# design.net
KiCad netlist of a schematic drawn in Altium Designer
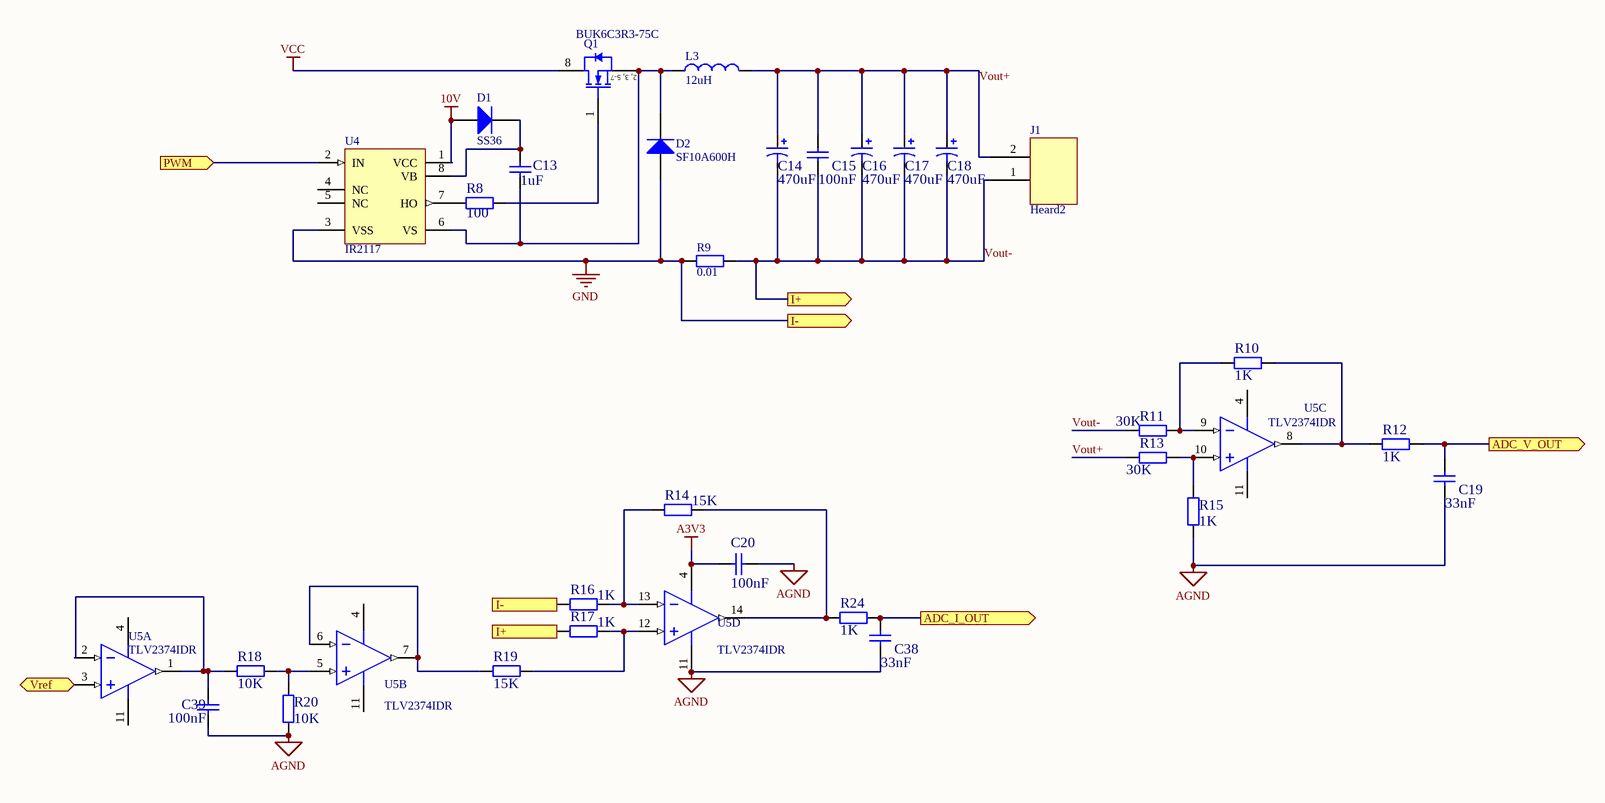
[diagram p0: 主电路.SchDoc]

(export (version "E")
  (design (tool "Eeschema 10.0.6"))
  (components
    (comp (ref "C13")
      (value "1uF")
      (footprint "0805R")
      (description "Capacitor")
      (fields (field (name "PUBLISHER") "Altium Limited"))
      (libsource (lib "Miscellaneous Devices") (part "Cap"))
    )
    (comp (ref "C14")
      (value "470uF")
      (footprint "RB-220T")
      (description "Polarized Capacitor (Radial)")
      (fields (field (name "Comment") "Cap Pol1") (field (name "PUBLISHER") "Altium Limited"))
      (libsource (lib "Miscellaneous Devices") (part "Cap Pol1"))
    )
    (comp (ref "C15")
      (value "100nF")
      (footprint "0805_C")
      (description "贴片电容")
      (libsource (lib "Miscellaneous Devices LC") (part "0805 100nF(104) 10% 50V"))
    )
    (comp (ref "C16")
      (value "470uF")
      (footprint "RB-220T")
      (description "Polarized Capacitor (Radial)")
      (fields (field (name "Comment") "Cap Pol1") (field (name "PUBLISHER") "Altium Limited"))
      (libsource (lib "Miscellaneous Devices") (part "Cap Pol1"))
    )
    (comp (ref "C17")
      (value "470uF")
      (footprint "RB-220T")
      (description "Polarized Capacitor (Radial)")
      (fields (field (name "Comment") "Cap Pol1") (field (name "PUBLISHER") "Altium Limited"))
      (libsource (lib "Miscellaneous Devices") (part "Cap Pol1"))
    )
    (comp (ref "C18")
      (value "470uF")
      (footprint "RB-220T")
      (description "Polarized Capacitor (Radial)")
      (fields (field (name "Comment") "Cap Pol1") (field (name "PUBLISHER") "Altium Limited"))
      (libsource (lib "Miscellaneous Devices") (part "Cap Pol1"))
    )
    (comp (ref "C19")
      (value "33nF")
      (footprint "0805_C")
      (description "贴片电容")
      (libsource (lib "Miscellaneous Devices LC") (part "0805 100nF(104) 10% 50V"))
    )
    (comp (ref "C20")
      (value "100nF")
      (footprint "0805_C")
      (description "贴片电容")
      (libsource (lib "Miscellaneous Devices LC") (part "0805 100nF(104) 10% 50V"))
    )
    (comp (ref "C38")
      (value "33nF")
      (footprint "0805_C")
      (description "贴片电容")
      (libsource (lib "Miscellaneous Devices LC") (part "0805 100nF(104) 10% 50V"))
    )
    (comp (ref "C39")
      (value "100nF")
      (footprint "0805_C")
      (description "贴片电容")
      (libsource (lib "Miscellaneous Devices LC") (part "0805 100nF(104) 10% 50V"))
    )
    (comp (ref "D1")
      (value "SS36")
      (footprint "SMC(DO-214AB)_S1")
      (description "二极管")
      (libsource (lib "Miscellaneous Devices LC") (part "SMC(DO-214AB) SS36-E3/57T"))
    )
    (comp (ref "D2")
      (value "SF10A600H")
      (footprint "SMC(DO-214AB)_S1")
      (description "二极管")
      (libsource (lib "Miscellaneous Devices LC") (part "SMC(DO-214AB) SS36-E3/57T"))
    )
    (comp (ref "J1")
      (value "Heard2")
      (footprint "8.5端子")
      (libsource (lib "myIntegrated_Library1") (part "Header2"))
    )
    (comp (ref "L3")
      (value "12uH")
      (footprint "L_12uh")
      (libsource (lib "myIntegrated_Library1") (part "L_12uh"))
    )
    (comp (ref "Q1")
      (value "BUK6C3R3-75C")
      (footprint "NXP-SOT427_N")
      (description "N-Channel TrenchMOS Intermediate Level FET, 75 V, 181 A, 7-Pin SOT427, Tape and Reel")
      (fields
        (field (name "MANUFACTURER") "NXP Semiconductors")
        (field (name "PARTNUMBER") "BUK6C3R3-75C,118")
      )
      (libsource (lib "NXP Semiconductors Automotive MOSFETs") (part "BUK6C3R3-75C,118"))
    )
    (comp (ref "R8")
      (value "100")
      (footprint "0805R")
      (description "Resistor")
      (fields (field (name "PUBLISHER") "Altium Limited"))
      (libsource (lib "Miscellaneous Devices") (part "Res2"))
    )
    (comp (ref "R9")
      (value "0.01")
      (footprint "水泥电阻")
      (libsource (lib "myIntegrated_Library1") (part "水泥电阻"))
    )
    (comp (ref "R10")
      (value "1K")
      (footprint "0805R")
      (description "Resistor")
      (fields (field (name "PUBLISHER") "Altium Limited"))
      (libsource (lib "Miscellaneous Devices") (part "Res2"))
    )
    (comp (ref "R11")
      (value "30K")
      (footprint "0805R")
      (description "Resistor")
      (fields (field (name "PUBLISHER") "Altium Limited"))
      (libsource (lib "") (part "Res2_1"))
    )
    (comp (ref "R12")
      (value "1K")
      (footprint "0805R")
      (description "Resistor")
      (fields (field (name "PUBLISHER") "Altium Limited"))
      (libsource (lib "Miscellaneous Devices") (part "Res2"))
    )
    (comp (ref "R13")
      (value "30K")
      (footprint "0805R")
      (description "Resistor")
      (fields (field (name "PUBLISHER") "Altium Limited"))
      (libsource (lib "") (part "Res2_1"))
    )
    (comp (ref "R14")
      (value "15K")
      (footprint "0805R")
      (description "Resistor")
      (fields (field (name "PUBLISHER") "Altium Limited"))
      (libsource (lib "") (part "Res2_1"))
    )
    (comp (ref "R15")
      (value "1K")
      (footprint "0805R")
      (description "Resistor")
      (fields (field (name "PUBLISHER") "Altium Limited"))
      (libsource (lib "") (part "Res2_2"))
    )
    (comp (ref "R16")
      (value "1K")
      (footprint "0805R")
      (description "Resistor")
      (fields (field (name "PUBLISHER") "Altium Limited"))
      (libsource (lib "") (part "Res2_1"))
    )
    (comp (ref "R17")
      (value "1K")
      (footprint "0805R")
      (description "Resistor")
      (fields (field (name "PUBLISHER") "Altium Limited"))
      (libsource (lib "") (part "Res2_1"))
    )
    (comp (ref "R18")
      (value "10K")
      (footprint "0805R")
      (description "Resistor")
      (fields (field (name "PUBLISHER") "Altium Limited"))
      (libsource (lib "Miscellaneous Devices") (part "Res2"))
    )
    (comp (ref "R19")
      (value "15K")
      (footprint "0805R")
      (description "Resistor")
      (fields (field (name "PUBLISHER") "Altium Limited"))
      (libsource (lib "Miscellaneous Devices") (part "Res2"))
    )
    (comp (ref "R20")
      (value "10K")
      (footprint "0805R")
      (description "Resistor")
      (fields (field (name "PUBLISHER") "Altium Limited"))
      (libsource (lib "") (part "Res2_2"))
    )
    (comp (ref "R24")
      (value "1K")
      (footprint "0805R")
      (description "Resistor")
      (fields (field (name "PUBLISHER") "Altium Limited"))
      (libsource (lib "Miscellaneous Devices") (part "Res2"))
    )
    (comp (ref "U4")
      (value "IR2117")
      (footprint "PDIP8")
      (description "Single Channel Driver")
      (fields (field (name "PUBLISHER") "Altium Limited"))
      (libsource (lib "altium-import") (part "root_0_IR2117_"))
    )
    (comp (ref "U5")
      (value "TLV2374IDR")
      (footprint "TI-D14_N")
      (fields (field (name "MANUFACTURER") "Texas Instruments"))
      (libsource (lib "TI Amplifiers and Linear Operational Amplifier Precision Amplifier Part Two") (part "TLV2374IDR"))
    )
  )
  (nets
    (net (code "1") (name "/ADC_I_OUT") (class "Default")
      (node (ref "C38") (pin "2") (pinfunction "2_2") (pintype "passive"))
      (node (ref "R24") (pin "2") (pinfunction "2_2") (pintype "passive"))
    )
    (net (code "2") (name "/ADC_V_OUT") (class "Default")
      (node (ref "C19") (pin "2") (pinfunction "2_2") (pintype "passive"))
      (node (ref "R12") (pin "2") (pinfunction "2_2") (pintype "passive"))
    )
    (net (code "3") (name "/PWM") (class "Default")
      (node (ref "U4") (pin "2") (pinfunction "IN_2") (pintype "input"))
    )
    (net (code "4") (name "/Vout+") (class "Default")
      (node (ref "C14") (pin "1") (pinfunction "1_1") (pintype "passive"))
      (node (ref "C15") (pin "2") (pinfunction "2_2") (pintype "passive"))
      (node (ref "C16") (pin "1") (pinfunction "1_1") (pintype "passive"))
      (node (ref "C17") (pin "1") (pinfunction "1_1") (pintype "passive"))
      (node (ref "C18") (pin "1") (pinfunction "1_1") (pintype "passive"))
      (node (ref "J1") (pin "2") (pinfunction "2_2") (pintype "passive"))
      (node (ref "L3") (pin "2") (pinfunction "2_2") (pintype "passive"))
      (node (ref "R13") (pin "2") (pinfunction "2_2") (pintype "passive"))
    )
    (net (code "5") (name "/Vout-") (class "Default")
      (node (ref "C14") (pin "2") (pinfunction "2_2") (pintype "passive"))
      (node (ref "C15") (pin "1") (pinfunction "1_1") (pintype "passive"))
      (node (ref "C16") (pin "2") (pinfunction "2_2") (pintype "passive"))
      (node (ref "C17") (pin "2") (pinfunction "2_2") (pintype "passive"))
      (node (ref "C18") (pin "2") (pinfunction "2_2") (pintype "passive"))
      (node (ref "J1") (pin "1") (pinfunction "1_1") (pintype "passive"))
      (node (ref "R11") (pin "2") (pinfunction "2_2") (pintype "passive"))
      (node (ref "R17") (pin "2") (pinfunction "2_2") (pintype "passive"))
      (node (ref "R9") (pin "2") (pinfunction "2_2") (pintype "passive"))
    )
    (net (code "6") (name "/Vref") (class "Default")
      (node (ref "U5") (pin "3") (pinfunction "IN1+_3") (pintype "input"))
    )
    (net (code "7") (name "10V") (class "Default")
      (node (ref "D1") (pin "1") (pinfunction "A_1") (pintype "passive"))
      (node (ref "U4") (pin "1") (pinfunction "VCC_1") (pintype "power_in"))
    )
    (net (code "8") (name "A3V3") (class "Default")
      (node (ref "C20") (pin "2") (pinfunction "2_2") (pintype "passive"))
      (node (ref "U5") (pin "4") (pinfunction "VDD_4") (pintype "power_in"))
    )
    (net (code "9") (name "AGND") (class "Default")
      (node (ref "C19") (pin "1") (pinfunction "1_1") (pintype "passive"))
      (node (ref "C20") (pin "1") (pinfunction "1_1") (pintype "passive"))
      (node (ref "C38") (pin "1") (pinfunction "1_1") (pintype "passive"))
      (node (ref "C39") (pin "1") (pinfunction "1_1") (pintype "passive"))
      (node (ref "R15") (pin "2") (pinfunction "2_2") (pintype "passive"))
      (node (ref "R20") (pin "2") (pinfunction "2_2") (pintype "passive"))
      (node (ref "U5") (pin "11") (pinfunction "GND_11") (pintype "power_in"))
    )
    (net (code "10") (name "GND") (class "Default")
      (node (ref "D2") (pin "1") (pinfunction "A_1") (pintype "passive"))
      (node (ref "R16") (pin "2") (pinfunction "2_2") (pintype "passive"))
      (node (ref "R9") (pin "1") (pinfunction "1_1") (pintype "passive"))
      (node (ref "U4") (pin "3") (pinfunction "VSS_3") (pintype "power_in"))
    )
    (net (code "11") (name "Net-(D1-K)") (class "Default")
      (node (ref "C13") (pin "1") (pinfunction "1_1") (pintype "passive"))
      (node (ref "D1") (pin "2") (pinfunction "K_2") (pintype "passive"))
      (node (ref "U4") (pin "8") (pinfunction "VB_8") (pintype "power_in"))
    )
    (net (code "12") (name "Net-(D2-K)") (class "Default")
      (node (ref "C13") (pin "2") (pinfunction "2_2") (pintype "passive"))
      (node (ref "D2") (pin "2") (pinfunction "K_2") (pintype "passive"))
      (node (ref "L3") (pin "1") (pinfunction "1_1") (pintype "passive"))
      (node (ref "Q1") (pin "2") (pinfunction "S_2") (pintype "passive"))
      (node (ref "Q1") (pin "3") (pinfunction "S_3") (pintype "passive"))
      (node (ref "Q1") (pin "5") (pinfunction "S_5") (pintype "passive"))
      (node (ref "Q1") (pin "6") (pinfunction "S_6") (pintype "passive"))
      (node (ref "Q1") (pin "7") (pinfunction "S_7") (pintype "passive"))
      (node (ref "U4") (pin "6") (pinfunction "VS_6") (pintype "power_in"))
    )
    (net (code "13") (name "Net-(Q1-G)") (class "Default")
      (node (ref "Q1") (pin "1") (pinfunction "G_1") (pintype "passive"))
      (node (ref "R8") (pin "2") (pinfunction "2_2") (pintype "passive"))
    )
    (net (code "14") (name "Net-(U4-HO)") (class "Default")
      (node (ref "R8") (pin "1") (pinfunction "1_1") (pintype "passive"))
      (node (ref "U4") (pin "7") (pinfunction "HO_7") (pintype "output"))
    )
    (net (code "15") (name "Net-(U5A-IN1-)") (class "Default")
      (node (ref "C39") (pin "2") (pinfunction "2_2") (pintype "passive"))
      (node (ref "R18") (pin "1") (pinfunction "1_1") (pintype "passive"))
      (node (ref "U5") (pin "1") (pinfunction "OUT1_1") (pintype "output"))
      (node (ref "U5") (pin "2") (pinfunction "IN1-_2") (pintype "input"))
    )
    (net (code "16") (name "Net-(U5B-IN2+)") (class "Default")
      (node (ref "R18") (pin "2") (pinfunction "2_2") (pintype "passive"))
      (node (ref "R20") (pin "1") (pinfunction "1_1") (pintype "passive"))
      (node (ref "U5") (pin "5") (pinfunction "IN2+_5") (pintype "input"))
    )
    (net (code "17") (name "Net-(U5B-IN2-)") (class "Default")
      (node (ref "R19") (pin "1") (pinfunction "1_1") (pintype "passive"))
      (node (ref "U5") (pin "6") (pinfunction "IN2-_6") (pintype "input"))
      (node (ref "U5") (pin "7") (pinfunction "OUT2_7") (pintype "output"))
    )
    (net (code "18") (name "Net-(U5C-IN3+)") (class "Default")
      (node (ref "R13") (pin "1") (pinfunction "1_1") (pintype "passive"))
      (node (ref "R15") (pin "1") (pinfunction "1_1") (pintype "passive"))
      (node (ref "U5") (pin "10") (pinfunction "IN3+_10") (pintype "input"))
    )
    (net (code "19") (name "Net-(U5C-IN3-)") (class "Default")
      (node (ref "R10") (pin "1") (pinfunction "1_1") (pintype "passive"))
      (node (ref "R11") (pin "1") (pinfunction "1_1") (pintype "passive"))
      (node (ref "U5") (pin "9") (pinfunction "IN3-_9") (pintype "input"))
    )
    (net (code "20") (name "Net-(U5C-OUT3)") (class "Default")
      (node (ref "R10") (pin "2") (pinfunction "2_2") (pintype "passive"))
      (node (ref "R12") (pin "1") (pinfunction "1_1") (pintype "passive"))
      (node (ref "U5") (pin "8") (pinfunction "OUT3_8") (pintype "output"))
    )
    (net (code "21") (name "Net-(U5D-IN4+)") (class "Default")
      (node (ref "R17") (pin "1") (pinfunction "1_1") (pintype "passive"))
      (node (ref "R19") (pin "2") (pinfunction "2_2") (pintype "passive"))
      (node (ref "U5") (pin "12") (pinfunction "IN4+_12") (pintype "input"))
    )
    (net (code "22") (name "Net-(U5D-IN4-)") (class "Default")
      (node (ref "R14") (pin "2") (pinfunction "2_2") (pintype "passive"))
      (node (ref "R16") (pin "1") (pinfunction "1_1") (pintype "passive"))
      (node (ref "U5") (pin "13") (pinfunction "IN4-_13") (pintype "input"))
    )
    (net (code "23") (name "Net-(U5D-OUT4)") (class "Default")
      (node (ref "R14") (pin "1") (pinfunction "1_1") (pintype "passive"))
      (node (ref "R24") (pin "1") (pinfunction "1_1") (pintype "passive"))
      (node (ref "U5") (pin "14") (pinfunction "OUT4_14") (pintype "output"))
    )
    (net (code "24") (name "VCC") (class "Default")
      (node (ref "Q1") (pin "8") (pinfunction "D_8") (pintype "passive"))
    )
    (net (code "25") (name "unconnected-(U4-NC-Pad4)") (class "Default")
      (node (ref "U4") (pin "4") (pinfunction "NC_4") (pintype "passive"))
    )
    (net (code "26") (name "unconnected-(U4-NC-Pad5)") (class "Default")
      (node (ref "U4") (pin "5") (pinfunction "NC_5") (pintype "passive"))
    )
    (net (code "27") (name "unconnected-(U5A-GND-Pad11)") (class "Default")
      (node (ref "U5") (pin "11") (pinfunction "GND_11") (pintype "power_in"))
    )
    (net (code "28") (name "unconnected-(U5A-VDD-Pad4)") (class "Default")
      (node (ref "U5") (pin "4") (pinfunction "VDD_4") (pintype "power_in"))
    )
    (net (code "29") (name "unconnected-(U5B-GND-Pad11)") (class "Default")
      (node (ref "U5") (pin "11") (pinfunction "GND_11") (pintype "power_in"))
    )
    (net (code "30") (name "unconnected-(U5B-VDD-Pad4)") (class "Default")
      (node (ref "U5") (pin "4") (pinfunction "VDD_4") (pintype "power_in"))
    )
    (net (code "31") (name "unconnected-(U5C-GND-Pad11)") (class "Default")
      (node (ref "U5") (pin "11") (pinfunction "GND_11") (pintype "power_in"))
    )
    (net (code "32") (name "unconnected-(U5C-VDD-Pad4)") (class "Default")
      (node (ref "U5") (pin "4") (pinfunction "VDD_4") (pintype "power_in"))
    )
  )
)
